# COUNTER2.net
KiCad netlist of a schematic drawn in EAGLE
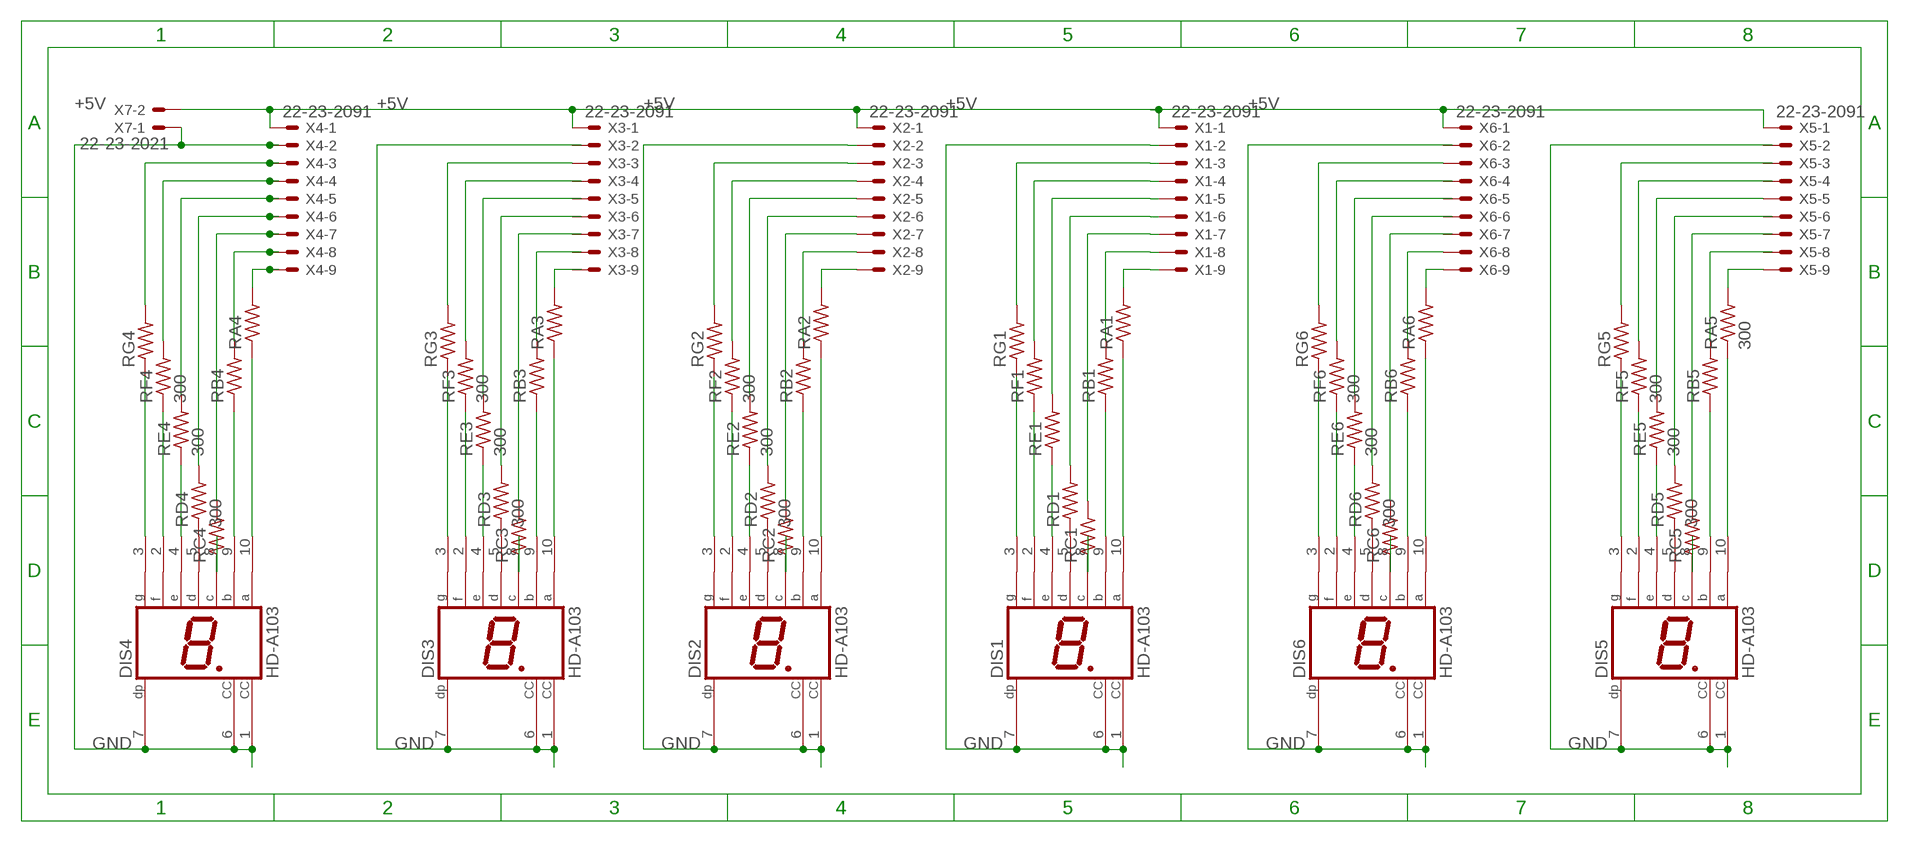
[diagram p0: schematic, sheet 1]

(export (version "E")
  (design (tool "Eeschema 10.0.6"))
  (components
    (comp (ref "DIS1")
      (value "HD-A103")
      (footprint "eagle-import:HDSP-A")
      (libsource (lib "eagle-import") (part "HD-A103"))
    )
    (comp (ref "DIS2")
      (value "HD-A103")
      (footprint "eagle-import:HDSP-A")
      (libsource (lib "eagle-import") (part "HD-A103"))
    )
    (comp (ref "DIS3")
      (value "HD-A103")
      (footprint "eagle-import:HDSP-A")
      (libsource (lib "eagle-import") (part "HD-A103"))
    )
    (comp (ref "DIS4")
      (value "HD-A103")
      (footprint "eagle-import:HDSP-A")
      (libsource (lib "eagle-import") (part "HD-A103"))
    )
    (comp (ref "DIS5")
      (value "HD-A103")
      (footprint "eagle-import:HDSP-A")
      (libsource (lib "eagle-import") (part "HD-A103"))
    )
    (comp (ref "DIS6")
      (value "HD-A103")
      (footprint "eagle-import:HDSP-A")
      (libsource (lib "eagle-import") (part "HD-A103"))
    )
    (comp (ref "RA1")
      (value "R-US_R0805")
      (footprint "eagle-import:R0805")
      (libsource (lib "eagle-import") (part "R-US_R0805"))
    )
    (comp (ref "RA2")
      (value "R-US_R0805")
      (footprint "eagle-import:R0805")
      (libsource (lib "eagle-import") (part "R-US_R0805"))
    )
    (comp (ref "RA3")
      (value "R-US_R0805")
      (footprint "eagle-import:R0805")
      (libsource (lib "eagle-import") (part "R-US_R0805"))
    )
    (comp (ref "RA4")
      (value "R-US_R0805")
      (footprint "eagle-import:R0805")
      (libsource (lib "eagle-import") (part "R-US_R0805"))
    )
    (comp (ref "RA5")
      (value "300")
      (footprint "eagle-import:R0805")
      (libsource (lib "eagle-import") (part "R-US_R0805"))
    )
    (comp (ref "RA6")
      (value "R-US_R0805")
      (footprint "eagle-import:R0805")
      (libsource (lib "eagle-import") (part "R-US_R0805"))
    )
    (comp (ref "RB1")
      (value "R-US_R0805")
      (footprint "eagle-import:R0805")
      (libsource (lib "eagle-import") (part "R-US_R0805"))
    )
    (comp (ref "RB2")
      (value "R-US_R0805")
      (footprint "eagle-import:R0805")
      (libsource (lib "eagle-import") (part "R-US_R0805"))
    )
    (comp (ref "RB3")
      (value "R-US_R0805")
      (footprint "eagle-import:R0805")
      (libsource (lib "eagle-import") (part "R-US_R0805"))
    )
    (comp (ref "RB4")
      (value "R-US_R0805")
      (footprint "eagle-import:R0805")
      (libsource (lib "eagle-import") (part "R-US_R0805"))
    )
    (comp (ref "RB5")
      (value "R-US_R0805")
      (footprint "eagle-import:R0805")
      (libsource (lib "eagle-import") (part "R-US_R0805"))
    )
    (comp (ref "RB6")
      (value "R-US_R0805")
      (footprint "eagle-import:R0805")
      (libsource (lib "eagle-import") (part "R-US_R0805"))
    )
    (comp (ref "RC1")
      (value "R-US_R0805")
      (footprint "eagle-import:R0805")
      (libsource (lib "eagle-import") (part "R-US_R0805"))
    )
    (comp (ref "RC2")
      (value "R-US_R0805")
      (footprint "eagle-import:R0805")
      (libsource (lib "eagle-import") (part "R-US_R0805"))
    )
    (comp (ref "RC3")
      (value "R-US_R0805")
      (footprint "eagle-import:R0805")
      (libsource (lib "eagle-import") (part "R-US_R0805"))
    )
    (comp (ref "RC4")
      (value "R-US_R0805")
      (footprint "eagle-import:R0805")
      (libsource (lib "eagle-import") (part "R-US_R0805"))
    )
    (comp (ref "RC5")
      (value "R-US_R0805")
      (footprint "eagle-import:R0805")
      (libsource (lib "eagle-import") (part "R-US_R0805"))
    )
    (comp (ref "RC6")
      (value "R-US_R0805")
      (footprint "eagle-import:R0805")
      (libsource (lib "eagle-import") (part "R-US_R0805"))
    )
    (comp (ref "RD1")
      (value "R-US_0204/5")
      (footprint "eagle-import:0204_5")
      (libsource (lib "eagle-import") (part "R-US_0204/5"))
    )
    (comp (ref "RD2")
      (value "300")
      (footprint "eagle-import:0204_5")
      (libsource (lib "eagle-import") (part "R-US_0204/5"))
    )
    (comp (ref "RD3")
      (value "300")
      (footprint "eagle-import:0204_5")
      (libsource (lib "eagle-import") (part "R-US_0204/5"))
    )
    (comp (ref "RD4")
      (value "300")
      (footprint "eagle-import:0204_5")
      (libsource (lib "eagle-import") (part "R-US_0204/5"))
    )
    (comp (ref "RD5")
      (value "300")
      (footprint "eagle-import:0204_5")
      (libsource (lib "eagle-import") (part "R-US_0204/5"))
    )
    (comp (ref "RD6")
      (value "300")
      (footprint "eagle-import:0204_5")
      (libsource (lib "eagle-import") (part "R-US_0204/5"))
    )
    (comp (ref "RE1")
      (value "R-US_0204/5")
      (footprint "eagle-import:0204_5")
      (libsource (lib "eagle-import") (part "R-US_0204/5"))
    )
    (comp (ref "RE2")
      (value "300")
      (footprint "eagle-import:0204_5")
      (libsource (lib "eagle-import") (part "R-US_0204/5"))
    )
    (comp (ref "RE3")
      (value "300")
      (footprint "eagle-import:0204_5")
      (libsource (lib "eagle-import") (part "R-US_0204/5"))
    )
    (comp (ref "RE4")
      (value "300")
      (footprint "eagle-import:0204_5")
      (libsource (lib "eagle-import") (part "R-US_0204/5"))
    )
    (comp (ref "RE5")
      (value "300")
      (footprint "eagle-import:0204_5")
      (libsource (lib "eagle-import") (part "R-US_0204/5"))
    )
    (comp (ref "RE6")
      (value "300")
      (footprint "eagle-import:0204_5")
      (libsource (lib "eagle-import") (part "R-US_0204/5"))
    )
    (comp (ref "RF1")
      (value "R-US_0204/5")
      (footprint "eagle-import:0204_5")
      (libsource (lib "eagle-import") (part "R-US_0204/5"))
    )
    (comp (ref "RF2")
      (value "300")
      (footprint "eagle-import:0204_5")
      (libsource (lib "eagle-import") (part "R-US_0204/5"))
    )
    (comp (ref "RF3")
      (value "300")
      (footprint "eagle-import:0204_5")
      (libsource (lib "eagle-import") (part "R-US_0204/5"))
    )
    (comp (ref "RF4")
      (value "300")
      (footprint "eagle-import:0204_5")
      (libsource (lib "eagle-import") (part "R-US_0204/5"))
    )
    (comp (ref "RF5")
      (value "300")
      (footprint "eagle-import:0204_5")
      (libsource (lib "eagle-import") (part "R-US_0204/5"))
    )
    (comp (ref "RF6")
      (value "300")
      (footprint "eagle-import:0204_5")
      (libsource (lib "eagle-import") (part "R-US_0204/5"))
    )
    (comp (ref "RG1")
      (value "R-US_0204/5")
      (footprint "eagle-import:0204_5")
      (libsource (lib "eagle-import") (part "R-US_0204/5"))
    )
    (comp (ref "RG2")
      (value "R-US_0204/5")
      (footprint "eagle-import:0204_5")
      (libsource (lib "eagle-import") (part "R-US_0204/5"))
    )
    (comp (ref "RG3")
      (value "R-US_0204/5")
      (footprint "eagle-import:0204_5")
      (libsource (lib "eagle-import") (part "R-US_0204/5"))
    )
    (comp (ref "RG4")
      (value "R-US_0204/5")
      (footprint "eagle-import:0204_5")
      (libsource (lib "eagle-import") (part "R-US_0204/5"))
    )
    (comp (ref "RG5")
      (value "R-US_0204/5")
      (footprint "eagle-import:0204_5")
      (libsource (lib "eagle-import") (part "R-US_0204/5"))
    )
    (comp (ref "RG6")
      (value "R-US_0204/5")
      (footprint "eagle-import:0204_5")
      (libsource (lib "eagle-import") (part "R-US_0204/5"))
    )
    (comp (ref "X1")
      (value "22-23-2091")
      (footprint "eagle-import:22-23-2091")
      (fields (field (name "MF") "MOLEX"))
      (libsource (lib "eagle-import") (part "22-23-2091"))
    )
    (comp (ref "X2")
      (value "22-23-2091")
      (footprint "eagle-import:22-23-2091")
      (fields (field (name "MF") "MOLEX"))
      (libsource (lib "eagle-import") (part "22-23-2091"))
    )
    (comp (ref "X3")
      (value "22-23-2091")
      (footprint "eagle-import:22-23-2091")
      (fields (field (name "MF") "MOLEX"))
      (libsource (lib "eagle-import") (part "22-23-2091"))
    )
    (comp (ref "X4")
      (value "22-23-2091")
      (footprint "eagle-import:22-23-2091")
      (fields (field (name "MF") "MOLEX"))
      (libsource (lib "eagle-import") (part "22-23-2091"))
    )
    (comp (ref "X5")
      (value "22-23-2091")
      (footprint "eagle-import:22-23-2091")
      (fields (field (name "MF") "MOLEX"))
      (libsource (lib "eagle-import") (part "22-23-2091"))
    )
    (comp (ref "X6")
      (value "22-23-2091")
      (footprint "eagle-import:22-23-2091")
      (fields (field (name "MF") "MOLEX"))
      (libsource (lib "eagle-import") (part "22-23-2091"))
    )
    (comp (ref "X7")
      (value "22-23-2021")
      (footprint "eagle-import:22-23-2021")
      (fields (field (name "MF") "MOLEX"))
      (libsource (lib "eagle-import") (part "22-23-2021"))
    )
  )
  (nets
    (net (code "1") (name "/+5V") (class "Default")
      (node (ref "X1") (pin "1") (pinfunction "S_1") (pintype "passive"))
      (node (ref "X2") (pin "1") (pinfunction "S_1") (pintype "passive"))
      (node (ref "X3") (pin "1") (pinfunction "S_1") (pintype "passive"))
      (node (ref "X4") (pin "1") (pinfunction "S_1") (pintype "passive"))
      (node (ref "X5") (pin "1") (pinfunction "S_1") (pintype "passive"))
      (node (ref "X6") (pin "1") (pinfunction "S_1") (pintype "passive"))
      (node (ref "X7") (pin "2") (pinfunction "S_2") (pintype "passive"))
    )
    (net (code "2") (name "/GND") (class "Default")
      (node (ref "DIS1") (pin "1") (pinfunction "CC_1") (pintype "passive"))
      (node (ref "DIS1") (pin "6") (pinfunction "CC_6") (pintype "passive"))
      (node (ref "DIS1") (pin "7") (pinfunction "DP_7") (pintype "passive"))
      (node (ref "DIS2") (pin "1") (pinfunction "CC_1") (pintype "passive"))
      (node (ref "DIS2") (pin "6") (pinfunction "CC_6") (pintype "passive"))
      (node (ref "DIS2") (pin "7") (pinfunction "DP_7") (pintype "passive"))
      (node (ref "DIS3") (pin "1") (pinfunction "CC_1") (pintype "passive"))
      (node (ref "DIS3") (pin "6") (pinfunction "CC_6") (pintype "passive"))
      (node (ref "DIS3") (pin "7") (pinfunction "DP_7") (pintype "passive"))
      (node (ref "DIS4") (pin "1") (pinfunction "CC_1") (pintype "passive"))
      (node (ref "DIS4") (pin "6") (pinfunction "CC_6") (pintype "passive"))
      (node (ref "DIS4") (pin "7") (pinfunction "DP_7") (pintype "passive"))
      (node (ref "DIS5") (pin "1") (pinfunction "CC_1") (pintype "passive"))
      (node (ref "DIS5") (pin "6") (pinfunction "CC_6") (pintype "passive"))
      (node (ref "DIS5") (pin "7") (pinfunction "DP_7") (pintype "passive"))
      (node (ref "DIS6") (pin "1") (pinfunction "CC_1") (pintype "passive"))
      (node (ref "DIS6") (pin "6") (pinfunction "CC_6") (pintype "passive"))
      (node (ref "DIS6") (pin "7") (pinfunction "DP_7") (pintype "passive"))
      (node (ref "X1") (pin "2") (pinfunction "S_2") (pintype "passive"))
      (node (ref "X2") (pin "2") (pinfunction "S_2") (pintype "passive"))
      (node (ref "X3") (pin "2") (pinfunction "S_2") (pintype "passive"))
      (node (ref "X4") (pin "2") (pinfunction "S_2") (pintype "passive"))
      (node (ref "X5") (pin "2") (pinfunction "S_2") (pintype "passive"))
      (node (ref "X6") (pin "2") (pinfunction "S_2") (pintype "passive"))
      (node (ref "X7") (pin "1") (pinfunction "S_1") (pintype "passive"))
    )
    (net (code "3") (name "Net-(DIS1-A)") (class "Default")
      (node (ref "DIS1") (pin "10") (pinfunction "A_10") (pintype "passive"))
      (node (ref "RA1") (pin "1") (pinfunction "1_1") (pintype "passive"))
    )
    (net (code "4") (name "Net-(DIS1-B)") (class "Default")
      (node (ref "DIS1") (pin "9") (pinfunction "B_9") (pintype "passive"))
      (node (ref "RB1") (pin "1") (pinfunction "1_1") (pintype "passive"))
    )
    (net (code "5") (name "Net-(DIS1-C)") (class "Default")
      (node (ref "DIS1") (pin "8") (pinfunction "C_8") (pintype "passive"))
      (node (ref "RC1") (pin "1") (pinfunction "1_1") (pintype "passive"))
    )
    (net (code "6") (name "Net-(DIS1-D)") (class "Default")
      (node (ref "DIS1") (pin "5") (pinfunction "D_5") (pintype "passive"))
      (node (ref "RD1") (pin "1") (pinfunction "1_1") (pintype "passive"))
    )
    (net (code "7") (name "Net-(DIS1-E)") (class "Default")
      (node (ref "DIS1") (pin "4") (pinfunction "E_4") (pintype "passive"))
      (node (ref "RE1") (pin "1") (pinfunction "1_1") (pintype "passive"))
    )
    (net (code "8") (name "Net-(DIS1-F)") (class "Default")
      (node (ref "DIS1") (pin "2") (pinfunction "F_2") (pintype "passive"))
      (node (ref "RF1") (pin "1") (pinfunction "1_1") (pintype "passive"))
    )
    (net (code "9") (name "Net-(DIS1-G)") (class "Default")
      (node (ref "DIS1") (pin "3") (pinfunction "G_3") (pintype "passive"))
      (node (ref "RG1") (pin "1") (pinfunction "1_1") (pintype "passive"))
    )
    (net (code "10") (name "Net-(DIS2-A)") (class "Default")
      (node (ref "DIS2") (pin "10") (pinfunction "A_10") (pintype "passive"))
      (node (ref "RA2") (pin "1") (pinfunction "1_1") (pintype "passive"))
    )
    (net (code "11") (name "Net-(DIS2-B)") (class "Default")
      (node (ref "DIS2") (pin "9") (pinfunction "B_9") (pintype "passive"))
      (node (ref "RB2") (pin "1") (pinfunction "1_1") (pintype "passive"))
    )
    (net (code "12") (name "Net-(DIS2-C)") (class "Default")
      (node (ref "DIS2") (pin "8") (pinfunction "C_8") (pintype "passive"))
      (node (ref "RC2") (pin "1") (pinfunction "1_1") (pintype "passive"))
    )
    (net (code "13") (name "Net-(DIS2-D)") (class "Default")
      (node (ref "DIS2") (pin "5") (pinfunction "D_5") (pintype "passive"))
      (node (ref "RD2") (pin "1") (pinfunction "1_1") (pintype "passive"))
    )
    (net (code "14") (name "Net-(DIS2-E)") (class "Default")
      (node (ref "DIS2") (pin "4") (pinfunction "E_4") (pintype "passive"))
      (node (ref "RE2") (pin "1") (pinfunction "1_1") (pintype "passive"))
    )
    (net (code "15") (name "Net-(DIS2-F)") (class "Default")
      (node (ref "DIS2") (pin "2") (pinfunction "F_2") (pintype "passive"))
      (node (ref "RF2") (pin "1") (pinfunction "1_1") (pintype "passive"))
    )
    (net (code "16") (name "Net-(DIS2-G)") (class "Default")
      (node (ref "DIS2") (pin "3") (pinfunction "G_3") (pintype "passive"))
      (node (ref "RG2") (pin "1") (pinfunction "1_1") (pintype "passive"))
    )
    (net (code "17") (name "Net-(DIS3-A)") (class "Default")
      (node (ref "DIS3") (pin "10") (pinfunction "A_10") (pintype "passive"))
      (node (ref "RA3") (pin "1") (pinfunction "1_1") (pintype "passive"))
    )
    (net (code "18") (name "Net-(DIS3-B)") (class "Default")
      (node (ref "DIS3") (pin "9") (pinfunction "B_9") (pintype "passive"))
      (node (ref "RB3") (pin "1") (pinfunction "1_1") (pintype "passive"))
    )
    (net (code "19") (name "Net-(DIS3-C)") (class "Default")
      (node (ref "DIS3") (pin "8") (pinfunction "C_8") (pintype "passive"))
      (node (ref "RC3") (pin "1") (pinfunction "1_1") (pintype "passive"))
    )
    (net (code "20") (name "Net-(DIS3-D)") (class "Default")
      (node (ref "DIS3") (pin "5") (pinfunction "D_5") (pintype "passive"))
      (node (ref "RD3") (pin "1") (pinfunction "1_1") (pintype "passive"))
    )
    (net (code "21") (name "Net-(DIS3-E)") (class "Default")
      (node (ref "DIS3") (pin "4") (pinfunction "E_4") (pintype "passive"))
      (node (ref "RE3") (pin "1") (pinfunction "1_1") (pintype "passive"))
    )
    (net (code "22") (name "Net-(DIS3-F)") (class "Default")
      (node (ref "DIS3") (pin "2") (pinfunction "F_2") (pintype "passive"))
      (node (ref "RF3") (pin "1") (pinfunction "1_1") (pintype "passive"))
    )
    (net (code "23") (name "Net-(DIS3-G)") (class "Default")
      (node (ref "DIS3") (pin "3") (pinfunction "G_3") (pintype "passive"))
      (node (ref "RG3") (pin "1") (pinfunction "1_1") (pintype "passive"))
    )
    (net (code "24") (name "Net-(DIS4-A)") (class "Default")
      (node (ref "DIS4") (pin "10") (pinfunction "A_10") (pintype "passive"))
      (node (ref "RA4") (pin "1") (pinfunction "1_1") (pintype "passive"))
    )
    (net (code "25") (name "Net-(DIS4-B)") (class "Default")
      (node (ref "DIS4") (pin "9") (pinfunction "B_9") (pintype "passive"))
      (node (ref "RB4") (pin "1") (pinfunction "1_1") (pintype "passive"))
    )
    (net (code "26") (name "Net-(DIS4-C)") (class "Default")
      (node (ref "DIS4") (pin "8") (pinfunction "C_8") (pintype "passive"))
      (node (ref "RC4") (pin "1") (pinfunction "1_1") (pintype "passive"))
    )
    (net (code "27") (name "Net-(DIS4-D)") (class "Default")
      (node (ref "DIS4") (pin "5") (pinfunction "D_5") (pintype "passive"))
      (node (ref "RD4") (pin "1") (pinfunction "1_1") (pintype "passive"))
    )
    (net (code "28") (name "Net-(DIS4-E)") (class "Default")
      (node (ref "DIS4") (pin "4") (pinfunction "E_4") (pintype "passive"))
      (node (ref "RE4") (pin "1") (pinfunction "1_1") (pintype "passive"))
    )
    (net (code "29") (name "Net-(DIS4-F)") (class "Default")
      (node (ref "DIS4") (pin "2") (pinfunction "F_2") (pintype "passive"))
      (node (ref "RF4") (pin "1") (pinfunction "1_1") (pintype "passive"))
    )
    (net (code "30") (name "Net-(DIS4-G)") (class "Default")
      (node (ref "DIS4") (pin "3") (pinfunction "G_3") (pintype "passive"))
      (node (ref "RG4") (pin "1") (pinfunction "1_1") (pintype "passive"))
    )
    (net (code "31") (name "Net-(DIS5-A)") (class "Default")
      (node (ref "DIS5") (pin "10") (pinfunction "A_10") (pintype "passive"))
      (node (ref "RA5") (pin "1") (pinfunction "1_1") (pintype "passive"))
    )
    (net (code "32") (name "Net-(DIS5-B)") (class "Default")
      (node (ref "DIS5") (pin "9") (pinfunction "B_9") (pintype "passive"))
      (node (ref "RB5") (pin "1") (pinfunction "1_1") (pintype "passive"))
    )
    (net (code "33") (name "Net-(DIS5-C)") (class "Default")
      (node (ref "DIS5") (pin "8") (pinfunction "C_8") (pintype "passive"))
      (node (ref "RC5") (pin "1") (pinfunction "1_1") (pintype "passive"))
    )
    (net (code "34") (name "Net-(DIS5-D)") (class "Default")
      (node (ref "DIS5") (pin "5") (pinfunction "D_5") (pintype "passive"))
      (node (ref "RD5") (pin "1") (pinfunction "1_1") (pintype "passive"))
    )
    (net (code "35") (name "Net-(DIS5-E)") (class "Default")
      (node (ref "DIS5") (pin "4") (pinfunction "E_4") (pintype "passive"))
      (node (ref "RE5") (pin "1") (pinfunction "1_1") (pintype "passive"))
    )
    (net (code "36") (name "Net-(DIS5-F)") (class "Default")
      (node (ref "DIS5") (pin "2") (pinfunction "F_2") (pintype "passive"))
      (node (ref "RF5") (pin "1") (pinfunction "1_1") (pintype "passive"))
    )
    (net (code "37") (name "Net-(DIS5-G)") (class "Default")
      (node (ref "DIS5") (pin "3") (pinfunction "G_3") (pintype "passive"))
      (node (ref "RG5") (pin "1") (pinfunction "1_1") (pintype "passive"))
    )
    (net (code "38") (name "Net-(DIS6-A)") (class "Default")
      (node (ref "DIS6") (pin "10") (pinfunction "A_10") (pintype "passive"))
      (node (ref "RA6") (pin "1") (pinfunction "1_1") (pintype "passive"))
    )
    (net (code "39") (name "Net-(DIS6-B)") (class "Default")
      (node (ref "DIS6") (pin "9") (pinfunction "B_9") (pintype "passive"))
      (node (ref "RB6") (pin "1") (pinfunction "1_1") (pintype "passive"))
    )
    (net (code "40") (name "Net-(DIS6-C)") (class "Default")
      (node (ref "DIS6") (pin "8") (pinfunction "C_8") (pintype "passive"))
      (node (ref "RC6") (pin "1") (pinfunction "1_1") (pintype "passive"))
    )
    (net (code "41") (name "Net-(DIS6-D)") (class "Default")
      (node (ref "DIS6") (pin "5") (pinfunction "D_5") (pintype "passive"))
      (node (ref "RD6") (pin "1") (pinfunction "1_1") (pintype "passive"))
    )
    (net (code "42") (name "Net-(DIS6-E)") (class "Default")
      (node (ref "DIS6") (pin "4") (pinfunction "E_4") (pintype "passive"))
      (node (ref "RE6") (pin "1") (pinfunction "1_1") (pintype "passive"))
    )
    (net (code "43") (name "Net-(DIS6-F)") (class "Default")
      (node (ref "DIS6") (pin "2") (pinfunction "F_2") (pintype "passive"))
      (node (ref "RF6") (pin "1") (pinfunction "1_1") (pintype "passive"))
    )
    (net (code "44") (name "Net-(DIS6-G)") (class "Default")
      (node (ref "DIS6") (pin "3") (pinfunction "G_3") (pintype "passive"))
      (node (ref "RG6") (pin "1") (pinfunction "1_1") (pintype "passive"))
    )
    (net (code "45") (name "Net-(X1C-S)") (class "Default")
      (node (ref "RG1") (pin "2") (pinfunction "2_2") (pintype "passive"))
      (node (ref "X1") (pin "3") (pinfunction "S_3") (pintype "passive"))
    )
    (net (code "46") (name "Net-(X1D-S)") (class "Default")
      (node (ref "RF1") (pin "2") (pinfunction "2_2") (pintype "passive"))
      (node (ref "X1") (pin "4") (pinfunction "S_4") (pintype "passive"))
    )
    (net (code "47") (name "Net-(X1E-S)") (class "Default")
      (node (ref "RE1") (pin "2") (pinfunction "2_2") (pintype "passive"))
      (node (ref "X1") (pin "5") (pinfunction "S_5") (pintype "passive"))
    )
    (net (code "48") (name "Net-(X1F-S)") (class "Default")
      (node (ref "RD1") (pin "2") (pinfunction "2_2") (pintype "passive"))
      (node (ref "X1") (pin "6") (pinfunction "S_6") (pintype "passive"))
    )
    (net (code "49") (name "Net-(X1G-S)") (class "Default")
      (node (ref "RC1") (pin "2") (pinfunction "2_2") (pintype "passive"))
      (node (ref "X1") (pin "7") (pinfunction "S_7") (pintype "passive"))
    )
    (net (code "50") (name "Net-(X1H-S)") (class "Default")
      (node (ref "RB1") (pin "2") (pinfunction "2_2") (pintype "passive"))
      (node (ref "X1") (pin "8") (pinfunction "S_8") (pintype "passive"))
    )
    (net (code "51") (name "Net-(X1I-S)") (class "Default")
      (node (ref "RA1") (pin "2") (pinfunction "2_2") (pintype "passive"))
      (node (ref "X1") (pin "9") (pinfunction "S_9") (pintype "passive"))
    )
    (net (code "52") (name "Net-(X2C-S)") (class "Default")
      (node (ref "RG2") (pin "2") (pinfunction "2_2") (pintype "passive"))
      (node (ref "X2") (pin "3") (pinfunction "S_3") (pintype "passive"))
    )
    (net (code "53") (name "Net-(X2D-S)") (class "Default")
      (node (ref "RF2") (pin "2") (pinfunction "2_2") (pintype "passive"))
      (node (ref "X2") (pin "4") (pinfunction "S_4") (pintype "passive"))
    )
    (net (code "54") (name "Net-(X2E-S)") (class "Default")
      (node (ref "RE2") (pin "2") (pinfunction "2_2") (pintype "passive"))
      (node (ref "X2") (pin "5") (pinfunction "S_5") (pintype "passive"))
    )
    (net (code "55") (name "Net-(X2F-S)") (class "Default")
      (node (ref "RD2") (pin "2") (pinfunction "2_2") (pintype "passive"))
      (node (ref "X2") (pin "6") (pinfunction "S_6") (pintype "passive"))
    )
    (net (code "56") (name "Net-(X2G-S)") (class "Default")
      (node (ref "RC2") (pin "2") (pinfunction "2_2") (pintype "passive"))
      (node (ref "X2") (pin "7") (pinfunction "S_7") (pintype "passive"))
    )
    (net (code "57") (name "Net-(X2H-S)") (class "Default")
      (node (ref "RB2") (pin "2") (pinfunction "2_2") (pintype "passive"))
      (node (ref "X2") (pin "8") (pinfunction "S_8") (pintype "passive"))
    )
    (net (code "58") (name "Net-(X2I-S)") (class "Default")
      (node (ref "RA2") (pin "2") (pinfunction "2_2") (pintype "passive"))
      (node (ref "X2") (pin "9") (pinfunction "S_9") (pintype "passive"))
    )
    (net (code "59") (name "Net-(X3C-S)") (class "Default")
      (node (ref "RG3") (pin "2") (pinfunction "2_2") (pintype "passive"))
      (node (ref "X3") (pin "3") (pinfunction "S_3") (pintype "passive"))
    )
    (net (code "60") (name "Net-(X3D-S)") (class "Default")
      (node (ref "RF3") (pin "2") (pinfunction "2_2") (pintype "passive"))
      (node (ref "X3") (pin "4") (pinfunction "S_4") (pintype "passive"))
    )
    (net (code "61") (name "Net-(X3E-S)") (class "Default")
      (node (ref "RE3") (pin "2") (pinfunction "2_2") (pintype "passive"))
      (node (ref "X3") (pin "5") (pinfunction "S_5") (pintype "passive"))
    )
    (net (code "62") (name "Net-(X3F-S)") (class "Default")
      (node (ref "RD3") (pin "2") (pinfunction "2_2") (pintype "passive"))
      (node (ref "X3") (pin "6") (pinfunction "S_6") (pintype "passive"))
    )
    (net (code "63") (name "Net-(X3G-S)") (class "Default")
      (node (ref "RC3") (pin "2") (pinfunction "2_2") (pintype "passive"))
      (node (ref "X3") (pin "7") (pinfunction "S_7") (pintype "passive"))
    )
    (net (code "64") (name "Net-(X3H-S)") (class "Default")
      (node (ref "RB3") (pin "2") (pinfunction "2_2") (pintype "passive"))
      (node (ref "X3") (pin "8") (pinfunction "S_8") (pintype "passive"))
    )
    (net (code "65") (name "Net-(X3I-S)") (class "Default")
      (node (ref "RA3") (pin "2") (pinfunction "2_2") (pintype "passive"))
      (node (ref "X3") (pin "9") (pinfunction "S_9") (pintype "passive"))
    )
    (net (code "66") (name "Net-(X4C-S)") (class "Default")
      (node (ref "RG4") (pin "2") (pinfunction "2_2") (pintype "passive"))
      (node (ref "X4") (pin "3") (pinfunction "S_3") (pintype "passive"))
    )
    (net (code "67") (name "Net-(X4D-S)") (class "Default")
      (node (ref "RF4") (pin "2") (pinfunction "2_2") (pintype "passive"))
      (node (ref "X4") (pin "4") (pinfunction "S_4") (pintype "passive"))
    )
    (net (code "68") (name "Net-(X4E-S)") (class "Default")
      (node (ref "RE4") (pin "2") (pinfunction "2_2") (pintype "passive"))
      (node (ref "X4") (pin "5") (pinfunction "S_5") (pintype "passive"))
    )
    (net (code "69") (name "Net-(X4F-S)") (class "Default")
      (node (ref "RD4") (pin "2") (pinfunction "2_2") (pintype "passive"))
      (node (ref "X4") (pin "6") (pinfunction "S_6") (pintype "passive"))
    )
    (net (code "70") (name "Net-(X4G-S)") (class "Default")
      (node (ref "RC4") (pin "2") (pinfunction "2_2") (pintype "passive"))
      (node (ref "X4") (pin "7") (pinfunction "S_7") (pintype "passive"))
    )
    (net (code "71") (name "Net-(X4H-S)") (class "Default")
      (node (ref "RB4") (pin "2") (pinfunction "2_2") (pintype "passive"))
      (node (ref "X4") (pin "8") (pinfunction "S_8") (pintype "passive"))
    )
    (net (code "72") (name "Net-(X4I-S)") (class "Default")
      (node (ref "RA4") (pin "2") (pinfunction "2_2") (pintype "passive"))
      (node (ref "X4") (pin "9") (pinfunction "S_9") (pintype "passive"))
    )
    (net (code "73") (name "Net-(X5C-S)") (class "Default")
      (node (ref "RG5") (pin "2") (pinfunction "2_2") (pintype "passive"))
      (node (ref "X5") (pin "3") (pinfunction "S_3") (pintype "passive"))
    )
    (net (code "74") (name "Net-(X5D-S)") (class "Default")
      (node (ref "RF5") (pin "2") (pinfunction "2_2") (pintype "passive"))
      (node (ref "X5") (pin "4") (pinfunction "S_4") (pintype "passive"))
    )
    (net (code "75") (name "Net-(X5E-S)") (class "Default")
      (node (ref "RE5") (pin "2") (pinfunction "2_2") (pintype "passive"))
      (node (ref "X5") (pin "5") (pinfunction "S_5") (pintype "passive"))
    )
    (net (code "76") (name "Net-(X5F-S)") (class "Default")
      (node (ref "RD5") (pin "2") (pinfunction "2_2") (pintype "passive"))
      (node (ref "X5") (pin "6") (pinfunction "S_6") (pintype "passive"))
    )
    (net (code "77") (name "Net-(X5G-S)") (class "Default")
      (node (ref "RC5") (pin "2") (pinfunction "2_2") (pintype "passive"))
      (node (ref "X5") (pin "7") (pinfunction "S_7") (pintype "passive"))
    )
    (net (code "78") (name "Net-(X5H-S)") (class "Default")
      (node (ref "RB5") (pin "2") (pinfunction "2_2") (pintype "passive"))
      (node (ref "X5") (pin "8") (pinfunction "S_8") (pintype "passive"))
    )
    (net (code "79") (name "Net-(X5I-S)") (class "Default")
      (node (ref "RA5") (pin "2") (pinfunction "2_2") (pintype "passive"))
      (node (ref "X5") (pin "9") (pinfunction "S_9") (pintype "passive"))
    )
    (net (code "80") (name "Net-(X6C-S)") (class "Default")
      (node (ref "RG6") (pin "2") (pinfunction "2_2") (pintype "passive"))
      (node (ref "X6") (pin "3") (pinfunction "S_3") (pintype "passive"))
    )
    (net (code "81") (name "Net-(X6D-S)") (class "Default")
      (node (ref "RF6") (pin "2") (pinfunction "2_2") (pintype "passive"))
      (node (ref "X6") (pin "4") (pinfunction "S_4") (pintype "passive"))
    )
    (net (code "82") (name "Net-(X6E-S)") (class "Default")
      (node (ref "RE6") (pin "2") (pinfunction "2_2") (pintype "passive"))
      (node (ref "X6") (pin "5") (pinfunction "S_5") (pintype "passive"))
    )
    (net (code "83") (name "Net-(X6F-S)") (class "Default")
      (node (ref "RD6") (pin "2") (pinfunction "2_2") (pintype "passive"))
      (node (ref "X6") (pin "6") (pinfunction "S_6") (pintype "passive"))
    )
    (net (code "84") (name "Net-(X6G-S)") (class "Default")
      (node (ref "RC6") (pin "2") (pinfunction "2_2") (pintype "passive"))
      (node (ref "X6") (pin "7") (pinfunction "S_7") (pintype "passive"))
    )
    (net (code "85") (name "Net-(X6H-S)") (class "Default")
      (node (ref "RB6") (pin "2") (pinfunction "2_2") (pintype "passive"))
      (node (ref "X6") (pin "8") (pinfunction "S_8") (pintype "passive"))
    )
    (net (code "86") (name "Net-(X6I-S)") (class "Default")
      (node (ref "RA6") (pin "2") (pinfunction "2_2") (pintype "passive"))
      (node (ref "X6") (pin "9") (pinfunction "S_9") (pintype "passive"))
    )
  )
)
